# satshakit_mini_fc.net
KiCad netlist of a schematic drawn in EAGLE
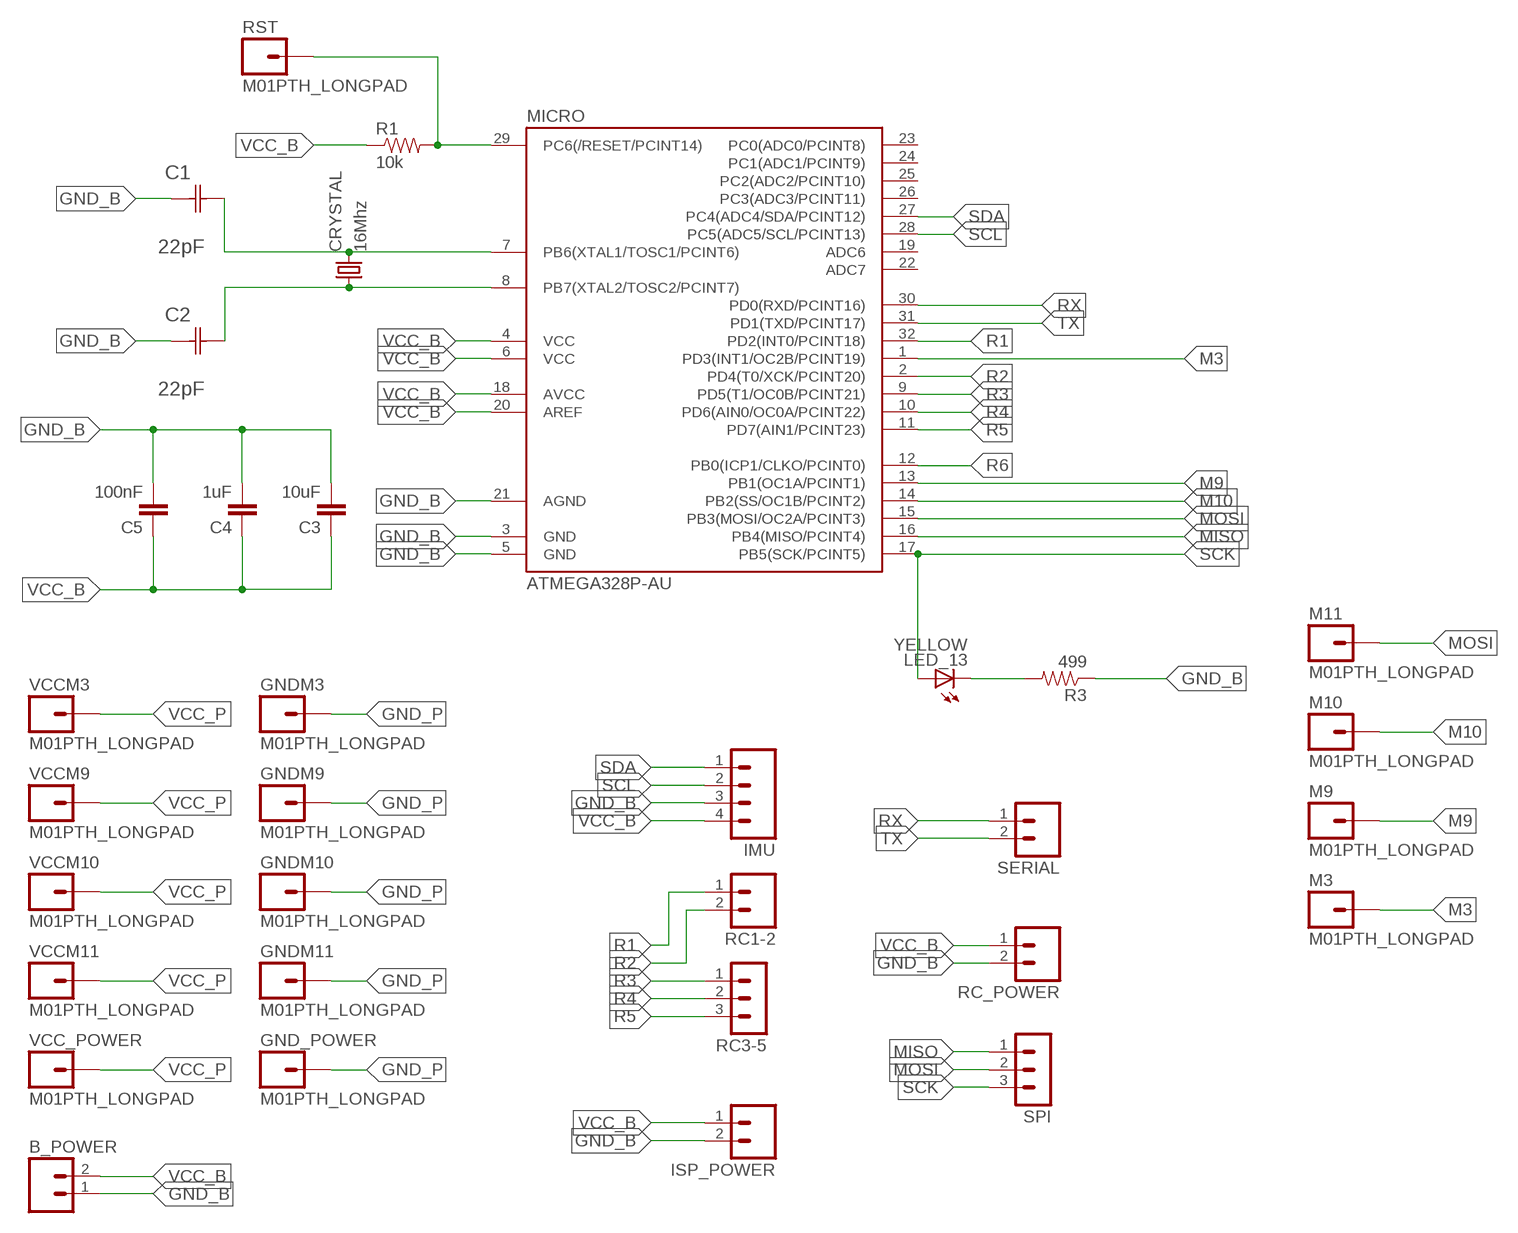
[diagram p0: schematic, sheet 1]

(export (version "E")
  (design (tool "Eeschema 10.0.6"))
  (components
    (comp (ref "B_POWER")
      (value "M02LOCK_LONGPADS")
      (footprint "eagle-import:1X02_LOCK_LONGPADS")
      (libsource (lib "eagle-import") (part "M02LOCK_LONGPADS"))
    )
    (comp (ref "C1")
      (value "22pF")
      (footprint "eagle-import:CAPC3216X178N")
      (fields (field (name "MPN") "0612ZC225MAT2A") (field (name "TOLERANCE") "±20%"))
      (libsource (lib "eagle-import") (part "0612ZC225MAT2A"))
    )
    (comp (ref "C2")
      (value "22pF")
      (footprint "eagle-import:CAPC3216X178N")
      (fields (field (name "MPN") "0612ZC225MAT2A") (field (name "TOLERANCE") "±20%"))
      (libsource (lib "eagle-import") (part "0612ZC225MAT2A"))
    )
    (comp (ref "C3")
      (value "10uF")
      (footprint "eagle-import:1206")
      (libsource (lib "eagle-import") (part "CAP1206"))
    )
    (comp (ref "C4")
      (value "1uF")
      (footprint "eagle-import:1206")
      (libsource (lib "eagle-import") (part "CAP1206"))
    )
    (comp (ref "C5")
      (value "100nF")
      (footprint "eagle-import:1206")
      (libsource (lib "eagle-import") (part "CAP1206"))
    )
    (comp (ref "CRYSTAL")
      (value "16Mhz")
      (footprint "eagle-import:CSM-7X-DU")
      (libsource (lib "eagle-import") (part "CSM-7X-DU"))
    )
    (comp (ref "GNDM3")
      (value "M01PTH_LONGPAD")
      (footprint "eagle-import:1X01_LONGPAD")
      (libsource (lib "eagle-import") (part "M01PTH_LONGPAD"))
    )
    (comp (ref "GNDM9")
      (value "M01PTH_LONGPAD")
      (footprint "eagle-import:1X01_LONGPAD")
      (libsource (lib "eagle-import") (part "M01PTH_LONGPAD"))
    )
    (comp (ref "GNDM10")
      (value "M01PTH_LONGPAD")
      (footprint "eagle-import:1X01_LONGPAD")
      (libsource (lib "eagle-import") (part "M01PTH_LONGPAD"))
    )
    (comp (ref "GNDM11")
      (value "M01PTH_LONGPAD")
      (footprint "eagle-import:1X01_LONGPAD")
      (libsource (lib "eagle-import") (part "M01PTH_LONGPAD"))
    )
    (comp (ref "GND_POWER")
      (value "M01PTH_LONGPAD")
      (footprint "eagle-import:1X01_LONGPAD")
      (libsource (lib "eagle-import") (part "M01PTH_LONGPAD"))
    )
    (comp (ref "IMU")
      (value "M04")
      (footprint "eagle-import:04P")
      (libsource (lib "eagle-import") (part "M04"))
    )
    (comp (ref "ISP_POWER")
      (value "M02LOCK_LONGPADS")
      (footprint "eagle-import:1X02_LOCK_LONGPADS")
      (libsource (lib "eagle-import") (part "M02LOCK_LONGPADS"))
    )
    (comp (ref "LED_13")
      (value "YELLOW")
      (footprint "eagle-import:1206")
      (libsource (lib "eagle-import") (part "LED1206"))
    )
    (comp (ref "M3")
      (value "M01PTH_LONGPAD")
      (footprint "eagle-import:1X01_LONGPAD")
      (libsource (lib "eagle-import") (part "M01PTH_LONGPAD"))
    )
    (comp (ref "M9")
      (value "M01PTH_LONGPAD")
      (footprint "eagle-import:1X01_LONGPAD")
      (libsource (lib "eagle-import") (part "M01PTH_LONGPAD"))
    )
    (comp (ref "M10")
      (value "M01PTH_LONGPAD")
      (footprint "eagle-import:1X01_LONGPAD")
      (libsource (lib "eagle-import") (part "M01PTH_LONGPAD"))
    )
    (comp (ref "M11")
      (value "M01PTH_LONGPAD")
      (footprint "eagle-import:1X01_LONGPAD")
      (libsource (lib "eagle-import") (part "M01PTH_LONGPAD"))
    )
    (comp (ref "MICRO")
      (value "ATMEGA328P-AU")
      (footprint "eagle-import:TQFP32-08")
      (libsource (lib "eagle-import") (part "ATMEGA48/88/168-AU"))
    )
    (comp (ref "R1")
      (value "10k")
      (footprint "eagle-import:1206")
      (libsource (lib "eagle-import") (part "RESISTOR1206"))
    )
    (comp (ref "R3")
      (value "499")
      (footprint "eagle-import:1206")
      (libsource (lib "eagle-import") (part "RESISTOR1206"))
    )
    (comp (ref "RC1-2")
      (value "M02")
      (footprint "eagle-import:02P")
      (libsource (lib "eagle-import") (part "con-amp-quick_M02"))
    )
    (comp (ref "RC3-5")
      (value "MA03-1")
      (footprint "eagle-import:MA03-1")
      (libsource (lib "eagle-import") (part "MA03-1"))
    )
    (comp (ref "RC_POWER")
      (value "M02LOCK_LONGPADS")
      (footprint "eagle-import:1X02_LOCK_LONGPADS")
      (libsource (lib "eagle-import") (part "M02LOCK_LONGPADS"))
    )
    (comp (ref "RST")
      (value "M01PTH_LONGPAD")
      (footprint "eagle-import:1X01_LONGPAD")
      (libsource (lib "eagle-import") (part "M01PTH_LONGPAD"))
    )
    (comp (ref "SERIAL")
      (value "M02LOCK_LONGPADS")
      (footprint "eagle-import:1X02_LOCK_LONGPADS")
      (libsource (lib "eagle-import") (part "M02LOCK_LONGPADS"))
    )
    (comp (ref "SPI")
      (value "MA03-1")
      (footprint "eagle-import:MA03-1")
      (libsource (lib "eagle-import") (part "MA03-1"))
    )
    (comp (ref "VCCM3")
      (value "M01PTH_LONGPAD")
      (footprint "eagle-import:1X01_LONGPAD")
      (libsource (lib "eagle-import") (part "M01PTH_LONGPAD"))
    )
    (comp (ref "VCCM9")
      (value "M01PTH_LONGPAD")
      (footprint "eagle-import:1X01_LONGPAD")
      (libsource (lib "eagle-import") (part "M01PTH_LONGPAD"))
    )
    (comp (ref "VCCM10")
      (value "M01PTH_LONGPAD")
      (footprint "eagle-import:1X01_LONGPAD")
      (libsource (lib "eagle-import") (part "M01PTH_LONGPAD"))
    )
    (comp (ref "VCCM11")
      (value "M01PTH_LONGPAD")
      (footprint "eagle-import:1X01_LONGPAD")
      (libsource (lib "eagle-import") (part "M01PTH_LONGPAD"))
    )
    (comp (ref "VCC_POWER")
      (value "M01PTH_LONGPAD")
      (footprint "eagle-import:1X01_LONGPAD")
      (libsource (lib "eagle-import") (part "M01PTH_LONGPAD"))
    )
  )
  (nets
    (net (code "1") (name "GND_B") (class "Default")
      (node (ref "B_POWER") (pin "1") (pinfunction "1_1") (pintype "passive"))
      (node (ref "C1") (pin "1") (pinfunction "C1_1") (pintype "passive"))
      (node (ref "C2") (pin "1") (pinfunction "C1_1") (pintype "passive"))
      (node (ref "C3") (pin "2") (pinfunction "2_2") (pintype "passive"))
      (node (ref "C4") (pin "2") (pinfunction "2_2") (pintype "passive"))
      (node (ref "C5") (pin "2") (pinfunction "2_2") (pintype "passive"))
      (node (ref "IMU") (pin "3") (pinfunction "3_3") (pintype "passive"))
      (node (ref "ISP_POWER") (pin "2") (pinfunction "2_2") (pintype "passive"))
      (node (ref "MICRO") (pin "21") (pinfunction "AGND_21") (pintype "power_in"))
      (node (ref "MICRO") (pin "3") (pinfunction "GND_3") (pintype "power_in"))
      (node (ref "MICRO") (pin "5") (pinfunction "GND_5") (pintype "power_in"))
      (node (ref "R3") (pin "1") (pinfunction "1_1") (pintype "passive"))
      (node (ref "RC_POWER") (pin "2") (pinfunction "2_2") (pintype "passive"))
    )
    (net (code "2") (name "GND_P") (class "Default")
      (node (ref "GNDM10") (pin "1") (pinfunction "1_1") (pintype "passive"))
      (node (ref "GNDM11") (pin "1") (pinfunction "1_1") (pintype "passive"))
      (node (ref "GNDM3") (pin "1") (pinfunction "1_1") (pintype "passive"))
      (node (ref "GNDM9") (pin "1") (pinfunction "1_1") (pintype "passive"))
      (node (ref "GND_POWER") (pin "1") (pinfunction "1_1") (pintype "passive"))
    )
    (net (code "3") (name "M3") (class "Default")
      (node (ref "M3") (pin "1") (pinfunction "1_1") (pintype "passive"))
      (node (ref "MICRO") (pin "1") (pinfunction "PD3(INT1/OC2B/PCINT19)_1") (pintype "bidirectional"))
    )
    (net (code "4") (name "M9") (class "Default")
      (node (ref "M9") (pin "1") (pinfunction "1_1") (pintype "passive"))
      (node (ref "MICRO") (pin "13") (pinfunction "PB1(OC1A/PCINT1)_13") (pintype "bidirectional"))
    )
    (net (code "5") (name "M10") (class "Default")
      (node (ref "M10") (pin "1") (pinfunction "1_1") (pintype "passive"))
      (node (ref "MICRO") (pin "14") (pinfunction "PB2(SS/OC1B/PCINT2)_14") (pintype "bidirectional"))
    )
    (net (code "6") (name "MISO") (class "Default")
      (node (ref "MICRO") (pin "16") (pinfunction "PB4(MISO/PCINT4)_16") (pintype "bidirectional"))
      (node (ref "SPI") (pin "1") (pinfunction "1_1") (pintype "passive"))
    )
    (net (code "7") (name "MOSI") (class "Default")
      (node (ref "M11") (pin "1") (pinfunction "1_1") (pintype "passive"))
      (node (ref "MICRO") (pin "15") (pinfunction "PB3(MOSI/OC2A/PCINT3)_15") (pintype "bidirectional"))
      (node (ref "SPI") (pin "2") (pinfunction "2_2") (pintype "passive"))
    )
    (net (code "8") (name "Net-(C1-C2)") (class "Default")
      (node (ref "C1") (pin "2") (pinfunction "C2_2") (pintype "passive"))
      (node (ref "CRYSTAL") (pin "2") (pinfunction "2_2") (pintype "passive"))
      (node (ref "MICRO") (pin "7") (pinfunction "PB6(XTAL1/TOSC1/PCINT6)_7") (pintype "bidirectional"))
    )
    (net (code "9") (name "Net-(C2-C2)") (class "Default")
      (node (ref "C2") (pin "2") (pinfunction "C2_2") (pintype "passive"))
      (node (ref "CRYSTAL") (pin "1") (pinfunction "1_1") (pintype "passive"))
      (node (ref "MICRO") (pin "8") (pinfunction "PB7(XTAL2/TOSC2/PCINT7)_8") (pintype "bidirectional"))
    )
    (net (code "10") (name "Net-(LED_13-C)") (class "Default")
      (node (ref "LED_13") (pin "2") (pinfunction "C_2") (pintype "passive"))
      (node (ref "R3") (pin "2") (pinfunction "2_2") (pintype "passive"))
    )
    (net (code "11") (name "Net-(MICRO-PC6({slash}RESET{slash}PCINT14))") (class "Default")
      (node (ref "MICRO") (pin "29") (pinfunction "PC6(/RESET/PCINT14)_29") (pintype "bidirectional"))
      (node (ref "R1") (pin "2") (pinfunction "2_2") (pintype "passive"))
      (node (ref "RST") (pin "1") (pinfunction "1_1") (pintype "passive"))
    )
    (net (code "12") (name "R1") (class "Default")
      (node (ref "MICRO") (pin "32") (pinfunction "PD2(INT0/PCINT18)_32") (pintype "bidirectional"))
      (node (ref "RC1-2") (pin "1") (pinfunction "1_1") (pintype "passive"))
    )
    (net (code "13") (name "R2") (class "Default")
      (node (ref "MICRO") (pin "2") (pinfunction "PD4(T0/XCK/PCINT20)_2") (pintype "bidirectional"))
      (node (ref "RC1-2") (pin "2") (pinfunction "2_2") (pintype "passive"))
    )
    (net (code "14") (name "R3") (class "Default")
      (node (ref "MICRO") (pin "9") (pinfunction "PD5(T1/OC0B/PCINT21)_9") (pintype "bidirectional"))
      (node (ref "RC3-5") (pin "1") (pinfunction "1_1") (pintype "passive"))
    )
    (net (code "15") (name "R4") (class "Default")
      (node (ref "MICRO") (pin "10") (pinfunction "PD6(AIN0/OC0A/PCINT22)_10") (pintype "bidirectional"))
      (node (ref "RC3-5") (pin "2") (pinfunction "2_2") (pintype "passive"))
    )
    (net (code "16") (name "R5") (class "Default")
      (node (ref "MICRO") (pin "11") (pinfunction "PD7(AIN1/PCINT23)_11") (pintype "bidirectional"))
      (node (ref "RC3-5") (pin "3") (pinfunction "3_3") (pintype "passive"))
    )
    (net (code "17") (name "R6") (class "Default")
      (node (ref "MICRO") (pin "12") (pinfunction "PB0(ICP1/CLKO/PCINT0)_12") (pintype "bidirectional"))
    )
    (net (code "18") (name "RX") (class "Default")
      (node (ref "MICRO") (pin "30") (pinfunction "PD0(RXD/PCINT16)_30") (pintype "bidirectional"))
      (node (ref "SERIAL") (pin "1") (pinfunction "1_1") (pintype "passive"))
    )
    (net (code "19") (name "SCK") (class "Default")
      (node (ref "LED_13") (pin "1") (pinfunction "A_1") (pintype "passive"))
      (node (ref "MICRO") (pin "17") (pinfunction "PB5(SCK/PCINT5)_17") (pintype "bidirectional"))
      (node (ref "SPI") (pin "3") (pinfunction "3_3") (pintype "passive"))
    )
    (net (code "20") (name "SCL") (class "Default")
      (node (ref "IMU") (pin "2") (pinfunction "2_2") (pintype "passive"))
      (node (ref "MICRO") (pin "28") (pinfunction "PC5(ADC5/SCL/PCINT13)_28") (pintype "bidirectional"))
    )
    (net (code "21") (name "SDA") (class "Default")
      (node (ref "IMU") (pin "1") (pinfunction "1_1") (pintype "passive"))
      (node (ref "MICRO") (pin "27") (pinfunction "PC4(ADC4/SDA/PCINT12)_27") (pintype "bidirectional"))
    )
    (net (code "22") (name "TX") (class "Default")
      (node (ref "MICRO") (pin "31") (pinfunction "PD1(TXD/PCINT17)_31") (pintype "bidirectional"))
      (node (ref "SERIAL") (pin "2") (pinfunction "2_2") (pintype "passive"))
    )
    (net (code "23") (name "VCC_B") (class "Default")
      (node (ref "B_POWER") (pin "2") (pinfunction "2_2") (pintype "passive"))
      (node (ref "C3") (pin "1") (pinfunction "1_1") (pintype "passive"))
      (node (ref "C4") (pin "1") (pinfunction "1_1") (pintype "passive"))
      (node (ref "C5") (pin "1") (pinfunction "1_1") (pintype "passive"))
      (node (ref "IMU") (pin "4") (pinfunction "4_4") (pintype "passive"))
      (node (ref "ISP_POWER") (pin "1") (pinfunction "1_1") (pintype "passive"))
      (node (ref "MICRO") (pin "18") (pinfunction "AVCC_18") (pintype "passive"))
      (node (ref "MICRO") (pin "20") (pinfunction "AREF_20") (pintype "passive"))
      (node (ref "MICRO") (pin "4") (pinfunction "VCC_4") (pintype "power_in"))
      (node (ref "MICRO") (pin "6") (pinfunction "VCC_6") (pintype "power_in"))
      (node (ref "R1") (pin "1") (pinfunction "1_1") (pintype "passive"))
      (node (ref "RC_POWER") (pin "1") (pinfunction "1_1") (pintype "passive"))
    )
    (net (code "24") (name "VCC_P") (class "Default")
      (node (ref "VCCM10") (pin "1") (pinfunction "1_1") (pintype "passive"))
      (node (ref "VCCM11") (pin "1") (pinfunction "1_1") (pintype "passive"))
      (node (ref "VCCM3") (pin "1") (pinfunction "1_1") (pintype "passive"))
      (node (ref "VCCM9") (pin "1") (pinfunction "1_1") (pintype "passive"))
      (node (ref "VCC_POWER") (pin "1") (pinfunction "1_1") (pintype "passive"))
    )
    (net (code "25") (name "unconnected-(MICRO-ADC6-Pad19)") (class "Default")
      (node (ref "MICRO") (pin "19") (pinfunction "ADC6_19") (pintype "passive"))
    )
    (net (code "26") (name "unconnected-(MICRO-ADC7-Pad22)") (class "Default")
      (node (ref "MICRO") (pin "22") (pinfunction "ADC7_22") (pintype "passive"))
    )
    (net (code "27") (name "unconnected-(MICRO-PC0(ADC0{slash}PCINT8)-Pad23)") (class "Default")
      (node (ref "MICRO") (pin "23") (pinfunction "PC0(ADC0/PCINT8)_23") (pintype "bidirectional"))
    )
    (net (code "28") (name "unconnected-(MICRO-PC1(ADC1{slash}PCINT9)-Pad24)") (class "Default")
      (node (ref "MICRO") (pin "24") (pinfunction "PC1(ADC1/PCINT9)_24") (pintype "bidirectional"))
    )
    (net (code "29") (name "unconnected-(MICRO-PC2(ADC2{slash}PCINT10)-Pad25)") (class "Default")
      (node (ref "MICRO") (pin "25") (pinfunction "PC2(ADC2/PCINT10)_25") (pintype "bidirectional"))
    )
    (net (code "30") (name "unconnected-(MICRO-PC3(ADC3{slash}PCINT11)-Pad26)") (class "Default")
      (node (ref "MICRO") (pin "26") (pinfunction "PC3(ADC3/PCINT11)_26") (pintype "bidirectional"))
    )
  )
)
